# Adder_1_1.net
KiCad netlist of a schematic drawn in EAGLE
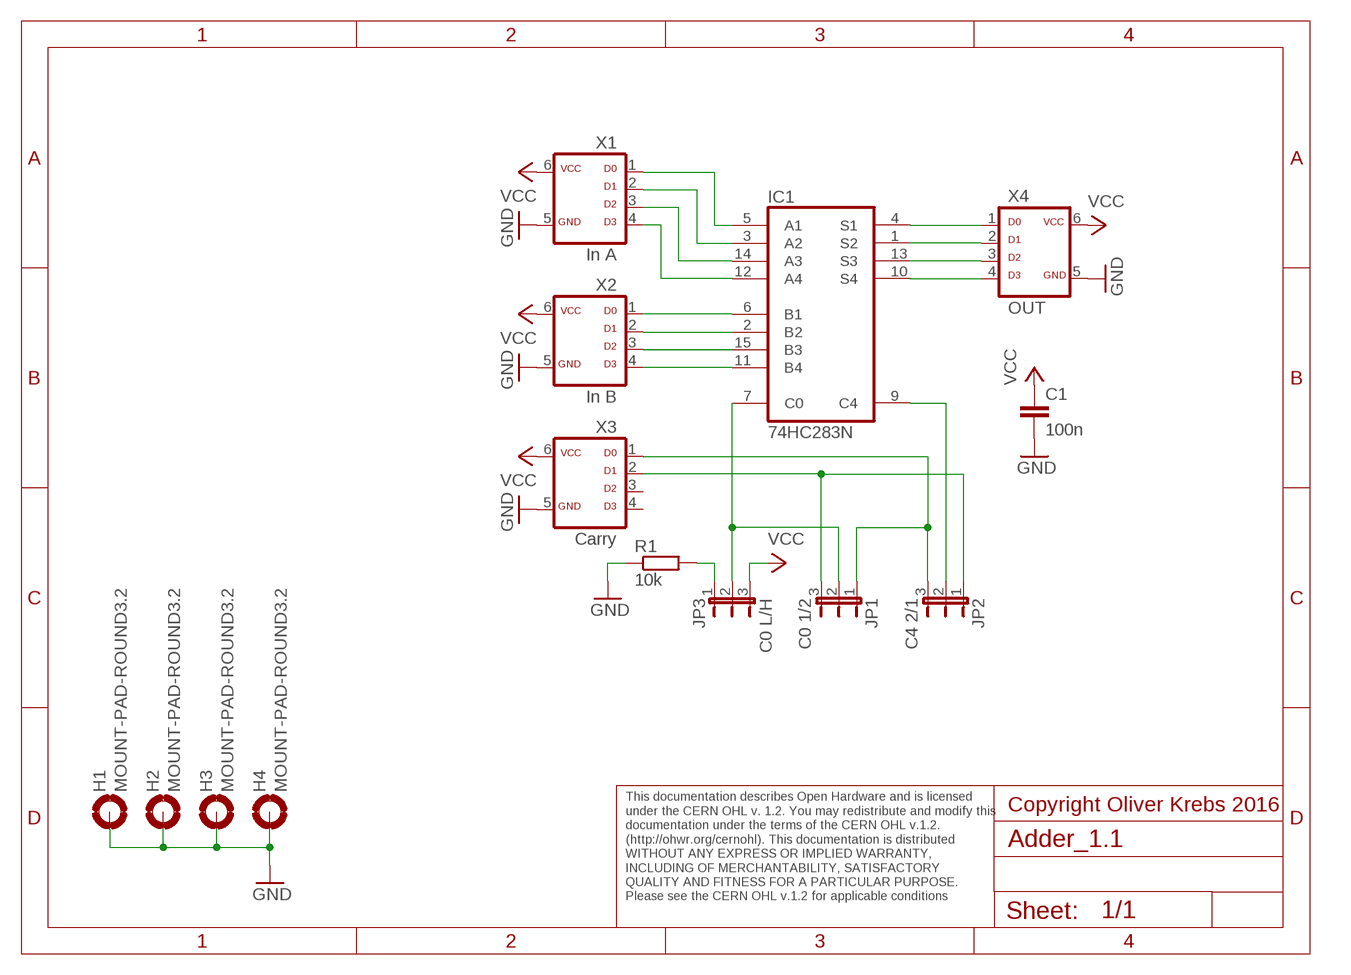
[diagram p0: schematic, sheet 1]

(export (version "E")
  (design (tool "Eeschema 10.0.6"))
  (components
    (comp (ref "C1")
      (value "100n")
      (footprint "eagle-import:C050-025X075")
      (libsource (lib "eagle-import") (part "C-EU050-025X075"))
    )
    (comp (ref "H1")
      (value "MOUNT-PAD-ROUND3.2")
      (footprint "eagle-import:3,2-PAD")
      (libsource (lib "eagle-import") (part "MOUNT-PAD-ROUND3.2"))
    )
    (comp (ref "H2")
      (value "MOUNT-PAD-ROUND3.2")
      (footprint "eagle-import:3,2-PAD")
      (libsource (lib "eagle-import") (part "MOUNT-PAD-ROUND3.2"))
    )
    (comp (ref "H3")
      (value "MOUNT-PAD-ROUND3.2")
      (footprint "eagle-import:3,2-PAD")
      (libsource (lib "eagle-import") (part "MOUNT-PAD-ROUND3.2"))
    )
    (comp (ref "H4")
      (value "MOUNT-PAD-ROUND3.2")
      (footprint "eagle-import:3,2-PAD")
      (libsource (lib "eagle-import") (part "MOUNT-PAD-ROUND3.2"))
    )
    (comp (ref "IC1")
      (value "74HC283N")
      (footprint "eagle-import:DIL16")
      (libsource (lib "eagle-import") (part "74283NHC"))
    )
    (comp (ref "JP1")
      (value "C0 1/2")
      (footprint "eagle-import:JP2")
      (libsource (lib "eagle-import") (part "JP2E"))
    )
    (comp (ref "JP2")
      (value "C4 2/1")
      (footprint "eagle-import:JP2")
      (libsource (lib "eagle-import") (part "JP2E"))
    )
    (comp (ref "JP3")
      (value "C0 L/H")
      (footprint "eagle-import:JP2")
      (libsource (lib "eagle-import") (part "JP2E"))
    )
    (comp (ref "R1")
      (value "10k")
      (footprint "eagle-import:0207_10")
      (libsource (lib "eagle-import") (part "R-EU_0207/10"))
    )
    (comp (ref "X1")
      (value "In A")
      (footprint "eagle-import:ML-6")
      (libsource (lib "eagle-import") (part "ML6D"))
    )
    (comp (ref "X2")
      (value "In B")
      (footprint "eagle-import:ML-6")
      (libsource (lib "eagle-import") (part "ML6D"))
    )
    (comp (ref "X3")
      (value "Carry")
      (footprint "eagle-import:ML-6")
      (libsource (lib "eagle-import") (part "ML6D"))
    )
    (comp (ref "X4")
      (value "OUT")
      (footprint "eagle-import:ML-6")
      (libsource (lib "eagle-import") (part "ML6D"))
    )
  )
  (nets
    (net (code "1") (name "GND") (class "Default")
      (node (ref "C1") (pin "2") (pinfunction "2_2") (pintype "passive"))
      (node (ref "H1") (pin "B3,2") (pinfunction "MOUNT_B3,2") (pintype "passive"))
      (node (ref "H2") (pin "B3,2") (pinfunction "MOUNT_B3,2") (pintype "passive"))
      (node (ref "H3") (pin "B3,2") (pinfunction "MOUNT_B3,2") (pintype "passive"))
      (node (ref "H4") (pin "B3,2") (pinfunction "MOUNT_B3,2") (pintype "passive"))
      (node (ref "R1") (pin "1") (pinfunction "1_1") (pintype "passive"))
      (node (ref "X1") (pin "5") (pinfunction "5_5") (pintype "passive"))
      (node (ref "X2") (pin "5") (pinfunction "5_5") (pintype "passive"))
      (node (ref "X3") (pin "5") (pinfunction "5_5") (pintype "passive"))
      (node (ref "X4") (pin "5") (pinfunction "5_5") (pintype "passive"))
    )
    (net (code "2") (name "Net-(IC1A-A1)") (class "Default")
      (node (ref "IC1") (pin "5") (pinfunction "A1_5") (pintype "input"))
      (node (ref "X1") (pin "1") (pinfunction "1_1") (pintype "passive"))
    )
    (net (code "3") (name "Net-(IC1A-A2)") (class "Default")
      (node (ref "IC1") (pin "3") (pinfunction "A2_3") (pintype "input"))
      (node (ref "X1") (pin "2") (pinfunction "2_2") (pintype "passive"))
    )
    (net (code "4") (name "Net-(IC1A-A3)") (class "Default")
      (node (ref "IC1") (pin "14") (pinfunction "A3_14") (pintype "input"))
      (node (ref "X1") (pin "3") (pinfunction "3_3") (pintype "passive"))
    )
    (net (code "5") (name "Net-(IC1A-A4)") (class "Default")
      (node (ref "IC1") (pin "12") (pinfunction "A4_12") (pintype "input"))
      (node (ref "X1") (pin "4") (pinfunction "4_4") (pintype "passive"))
    )
    (net (code "6") (name "Net-(IC1A-B1)") (class "Default")
      (node (ref "IC1") (pin "6") (pinfunction "B1_6") (pintype "input"))
      (node (ref "X2") (pin "1") (pinfunction "1_1") (pintype "passive"))
    )
    (net (code "7") (name "Net-(IC1A-B2)") (class "Default")
      (node (ref "IC1") (pin "2") (pinfunction "B2_2") (pintype "input"))
      (node (ref "X2") (pin "2") (pinfunction "2_2") (pintype "passive"))
    )
    (net (code "8") (name "Net-(IC1A-B3)") (class "Default")
      (node (ref "IC1") (pin "15") (pinfunction "B3_15") (pintype "input"))
      (node (ref "X2") (pin "3") (pinfunction "3_3") (pintype "passive"))
    )
    (net (code "9") (name "Net-(IC1A-B4)") (class "Default")
      (node (ref "IC1") (pin "11") (pinfunction "B4_11") (pintype "input"))
      (node (ref "X2") (pin "4") (pinfunction "4_4") (pintype "passive"))
    )
    (net (code "10") (name "Net-(IC1A-C0)") (class "Default")
      (node (ref "IC1") (pin "7") (pinfunction "C0_7") (pintype "input"))
      (node (ref "JP1") (pin "2") (pinfunction "2_2") (pintype "passive"))
      (node (ref "JP3") (pin "2") (pinfunction "2_2") (pintype "passive"))
    )
    (net (code "11") (name "Net-(IC1A-C4)") (class "Default")
      (node (ref "IC1") (pin "9") (pinfunction "C4_9") (pintype "output"))
      (node (ref "JP2") (pin "2") (pinfunction "2_2") (pintype "passive"))
    )
    (net (code "12") (name "Net-(IC1A-S1)") (class "Default")
      (node (ref "IC1") (pin "4") (pinfunction "S1_4") (pintype "output"))
      (node (ref "X4") (pin "1") (pinfunction "1_1") (pintype "passive"))
    )
    (net (code "13") (name "Net-(IC1A-S2)") (class "Default")
      (node (ref "IC1") (pin "1") (pinfunction "S2_1") (pintype "output"))
      (node (ref "X4") (pin "2") (pinfunction "2_2") (pintype "passive"))
    )
    (net (code "14") (name "Net-(IC1A-S3)") (class "Default")
      (node (ref "IC1") (pin "13") (pinfunction "S3_13") (pintype "output"))
      (node (ref "X4") (pin "3") (pinfunction "3_3") (pintype "passive"))
    )
    (net (code "15") (name "Net-(IC1A-S4)") (class "Default")
      (node (ref "IC1") (pin "10") (pinfunction "S4_10") (pintype "output"))
      (node (ref "X4") (pin "4") (pinfunction "4_4") (pintype "passive"))
    )
    (net (code "16") (name "Net-(JP1-Pad1)") (class "Default")
      (node (ref "JP1") (pin "1") (pinfunction "1_1") (pintype "passive"))
      (node (ref "JP2") (pin "3") (pinfunction "3_3") (pintype "passive"))
      (node (ref "X3") (pin "1") (pinfunction "1_1") (pintype "passive"))
    )
    (net (code "17") (name "Net-(JP1-Pad3)") (class "Default")
      (node (ref "JP1") (pin "3") (pinfunction "3_3") (pintype "passive"))
      (node (ref "JP2") (pin "1") (pinfunction "1_1") (pintype "passive"))
      (node (ref "X3") (pin "2") (pinfunction "2_2") (pintype "passive"))
    )
    (net (code "18") (name "Net-(JP3-Pad1)") (class "Default")
      (node (ref "JP3") (pin "1") (pinfunction "1_1") (pintype "passive"))
      (node (ref "R1") (pin "2") (pinfunction "2_2") (pintype "passive"))
    )
    (net (code "19") (name "VCC") (class "Default")
      (node (ref "C1") (pin "1") (pinfunction "1_1") (pintype "passive"))
      (node (ref "JP3") (pin "3") (pinfunction "3_3") (pintype "passive"))
      (node (ref "X1") (pin "6") (pinfunction "6_6") (pintype "passive"))
      (node (ref "X2") (pin "6") (pinfunction "6_6") (pintype "passive"))
      (node (ref "X3") (pin "6") (pinfunction "6_6") (pintype "passive"))
      (node (ref "X4") (pin "6") (pinfunction "6_6") (pintype "passive"))
    )
    (net (code "20") (name "unconnected-(X3-Pad3)") (class "Default")
      (node (ref "X3") (pin "3") (pinfunction "3_3") (pintype "passive"))
    )
    (net (code "21") (name "unconnected-(X3-Pad4)") (class "Default")
      (node (ref "X3") (pin "4") (pinfunction "4_4") (pintype "passive"))
    )
  )
)
